# Ex_8_LED_PCB_SMD_OPM-AMP.net
KiCad netlist of a schematic drawn in EAGLE
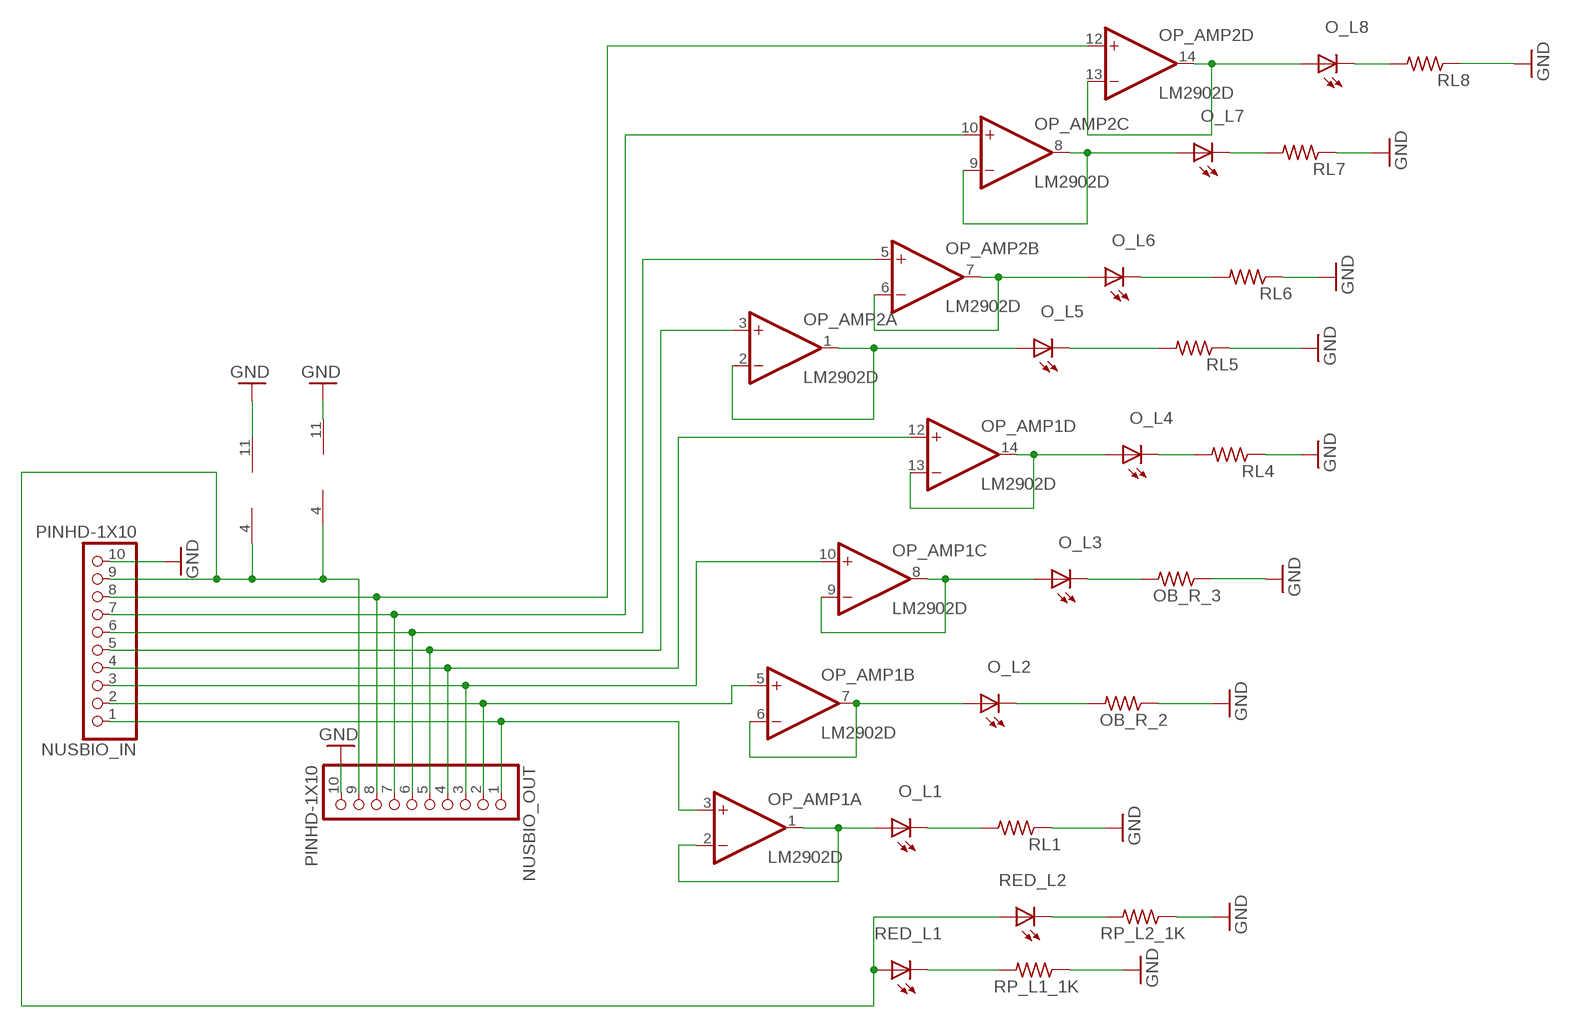
[diagram p0: schematic, sheet 1]

(export (version "E")
  (design (tool "Eeschema 10.0.6"))
  (components
    (comp (ref "NUSBIO_IN")
      (value "PINHD-1X10")
      (footprint "eagle-import:1X10-BIG")
      (libsource (lib "eagle-import") (part "PINHD-1X10"))
    )
    (comp (ref "NUSBIO_OUT")
      (value "PINHD-1X10")
      (footprint "eagle-import:1X10-BIG")
      (libsource (lib "eagle-import") (part "PINHD-1X10"))
    )
    (comp (ref "OB_R_2")
      (value "R-US_R0805")
      (footprint "eagle-import:R0805")
      (libsource (lib "eagle-import") (part "R-US_R0805"))
    )
    (comp (ref "OB_R_3")
      (value "R-US_R0805")
      (footprint "eagle-import:R0805")
      (libsource (lib "eagle-import") (part "R-US_R0805"))
    )
    (comp (ref "OP_AMP1")
      (value "LM2902D")
      (footprint "eagle-import:SO14")
      (libsource (lib "eagle-import") (part "LM2902D"))
    )
    (comp (ref "OP_AMP2")
      (value "LM2902D")
      (footprint "eagle-import:SO14")
      (libsource (lib "eagle-import") (part "LM2902D"))
    )
    (comp (ref "O_L1")
      (value "LEDCHIPLED_0805")
      (footprint "eagle-import:CHIPLED_0805")
      (libsource (lib "eagle-import") (part "LEDCHIPLED_0805"))
    )
    (comp (ref "O_L2")
      (value "LEDCHIPLED_0805")
      (footprint "eagle-import:CHIPLED_0805")
      (libsource (lib "eagle-import") (part "LEDCHIPLED_0805"))
    )
    (comp (ref "O_L3")
      (value "LEDCHIPLED_0805")
      (footprint "eagle-import:CHIPLED_0805")
      (libsource (lib "eagle-import") (part "LEDCHIPLED_0805"))
    )
    (comp (ref "O_L4")
      (value "LEDCHIPLED_0805")
      (footprint "eagle-import:CHIPLED_0805")
      (libsource (lib "eagle-import") (part "LEDCHIPLED_0805"))
    )
    (comp (ref "O_L5")
      (value "LEDCHIPLED_0805")
      (footprint "eagle-import:CHIPLED_0805")
      (libsource (lib "eagle-import") (part "LEDCHIPLED_0805"))
    )
    (comp (ref "O_L6")
      (value "LEDCHIPLED_0805")
      (footprint "eagle-import:CHIPLED_0805")
      (libsource (lib "eagle-import") (part "LEDCHIPLED_0805"))
    )
    (comp (ref "O_L7")
      (value "LEDCHIPLED_0805")
      (footprint "eagle-import:CHIPLED_0805")
      (libsource (lib "eagle-import") (part "LEDCHIPLED_0805"))
    )
    (comp (ref "O_L8")
      (value "LEDCHIPLED_0805")
      (footprint "eagle-import:CHIPLED_0805")
      (libsource (lib "eagle-import") (part "LEDCHIPLED_0805"))
    )
    (comp (ref "RED_L1")
      (value "LEDCHIPLED_0805")
      (footprint "eagle-import:CHIPLED_0805")
      (libsource (lib "eagle-import") (part "LEDCHIPLED_0805"))
    )
    (comp (ref "RED_L2")
      (value "LEDCHIPLED_0805")
      (footprint "eagle-import:CHIPLED_0805")
      (libsource (lib "eagle-import") (part "LEDCHIPLED_0805"))
    )
    (comp (ref "RL1")
      (value "R-US_R0805")
      (footprint "eagle-import:R0805")
      (libsource (lib "eagle-import") (part "R-US_R0805"))
    )
    (comp (ref "RL4")
      (value "R-US_R0805")
      (footprint "eagle-import:R0805")
      (libsource (lib "eagle-import") (part "R-US_R0805"))
    )
    (comp (ref "RL5")
      (value "R-US_R0805")
      (footprint "eagle-import:R0805")
      (libsource (lib "eagle-import") (part "R-US_R0805"))
    )
    (comp (ref "RL6")
      (value "R-US_R0805")
      (footprint "eagle-import:R0805")
      (libsource (lib "eagle-import") (part "R-US_R0805"))
    )
    (comp (ref "RL7")
      (value "R-US_R0805")
      (footprint "eagle-import:R0805")
      (libsource (lib "eagle-import") (part "R-US_R0805"))
    )
    (comp (ref "RL8")
      (value "R-US_R0805")
      (footprint "eagle-import:R0805")
      (libsource (lib "eagle-import") (part "R-US_R0805"))
    )
    (comp (ref "RP_L1_1K")
      (value "R-US_R0805")
      (footprint "eagle-import:R0805")
      (libsource (lib "eagle-import") (part "R-US_R0805"))
    )
    (comp (ref "RP_L2_1K")
      (value "R-US_R0805")
      (footprint "eagle-import:R0805")
      (libsource (lib "eagle-import") (part "R-US_R0805"))
    )
  )
  (nets
    (net (code "1") (name "GND") (class "Default")
      (node (ref "NUSBIO_IN") (pin "10") (pinfunction "10_10") (pintype "passive"))
      (node (ref "NUSBIO_OUT") (pin "10") (pinfunction "10_10") (pintype "passive"))
      (node (ref "OB_R_2") (pin "1") (pinfunction "1_1") (pintype "passive"))
      (node (ref "OB_R_3") (pin "1") (pinfunction "1_1") (pintype "passive"))
      (node (ref "OP_AMP1") (pin "11") (pinfunction "V-_11") (pintype "power_in"))
      (node (ref "OP_AMP2") (pin "11") (pinfunction "V-_11") (pintype "power_in"))
      (node (ref "RL1") (pin "1") (pinfunction "1_1") (pintype "passive"))
      (node (ref "RL4") (pin "1") (pinfunction "1_1") (pintype "passive"))
      (node (ref "RL5") (pin "1") (pinfunction "1_1") (pintype "passive"))
      (node (ref "RL6") (pin "1") (pinfunction "1_1") (pintype "passive"))
      (node (ref "RL7") (pin "1") (pinfunction "1_1") (pintype "passive"))
      (node (ref "RL8") (pin "1") (pinfunction "1_1") (pintype "passive"))
      (node (ref "RP_L1_1K") (pin "1") (pinfunction "1_1") (pintype "passive"))
      (node (ref "RP_L2_1K") (pin "1") (pinfunction "1_1") (pintype "passive"))
    )
    (net (code "2") (name "Net-(OB_R_2-Pad2)") (class "Default")
      (node (ref "OB_R_2") (pin "2") (pinfunction "2_2") (pintype "passive"))
      (node (ref "O_L2") (pin "C") (pinfunction "C_C") (pintype "passive"))
    )
    (net (code "3") (name "Net-(OB_R_3-Pad2)") (class "Default")
      (node (ref "OB_R_3") (pin "2") (pinfunction "2_2") (pintype "passive"))
      (node (ref "O_L3") (pin "C") (pinfunction "C_C") (pintype "passive"))
    )
    (net (code "4") (name "Net-(OP_AMP1A-+IN)") (class "Default")
      (node (ref "NUSBIO_IN") (pin "1") (pinfunction "1_1") (pintype "passive"))
      (node (ref "NUSBIO_OUT") (pin "1") (pinfunction "1_1") (pintype "passive"))
      (node (ref "OP_AMP1") (pin "3") (pinfunction "+IN_3") (pintype "input"))
    )
    (net (code "5") (name "Net-(OP_AMP1A--IN)") (class "Default")
      (node (ref "OP_AMP1") (pin "1") (pinfunction "OUT_1") (pintype "output"))
      (node (ref "OP_AMP1") (pin "2") (pinfunction "-IN_2") (pintype "input"))
      (node (ref "O_L1") (pin "A") (pinfunction "A_A") (pintype "passive"))
    )
    (net (code "6") (name "Net-(OP_AMP1B-+IN)") (class "Default")
      (node (ref "NUSBIO_IN") (pin "2") (pinfunction "2_2") (pintype "passive"))
      (node (ref "NUSBIO_OUT") (pin "2") (pinfunction "2_2") (pintype "passive"))
      (node (ref "OP_AMP1") (pin "5") (pinfunction "+IN_5") (pintype "input"))
    )
    (net (code "7") (name "Net-(OP_AMP1B--IN)") (class "Default")
      (node (ref "OP_AMP1") (pin "6") (pinfunction "-IN_6") (pintype "input"))
      (node (ref "OP_AMP1") (pin "7") (pinfunction "OUT_7") (pintype "output"))
      (node (ref "O_L2") (pin "A") (pinfunction "A_A") (pintype "passive"))
    )
    (net (code "8") (name "Net-(OP_AMP1C-+IN)") (class "Default")
      (node (ref "NUSBIO_IN") (pin "3") (pinfunction "3_3") (pintype "passive"))
      (node (ref "NUSBIO_OUT") (pin "3") (pinfunction "3_3") (pintype "passive"))
      (node (ref "OP_AMP1") (pin "10") (pinfunction "+IN_10") (pintype "input"))
    )
    (net (code "9") (name "Net-(OP_AMP1C--IN)") (class "Default")
      (node (ref "OP_AMP1") (pin "8") (pinfunction "OUT_8") (pintype "output"))
      (node (ref "OP_AMP1") (pin "9") (pinfunction "-IN_9") (pintype "input"))
      (node (ref "O_L3") (pin "A") (pinfunction "A_A") (pintype "passive"))
    )
    (net (code "10") (name "Net-(OP_AMP1D-+IN)") (class "Default")
      (node (ref "NUSBIO_IN") (pin "4") (pinfunction "4_4") (pintype "passive"))
      (node (ref "NUSBIO_OUT") (pin "4") (pinfunction "4_4") (pintype "passive"))
      (node (ref "OP_AMP1") (pin "12") (pinfunction "+IN_12") (pintype "input"))
    )
    (net (code "11") (name "Net-(OP_AMP1D--IN)") (class "Default")
      (node (ref "OP_AMP1") (pin "13") (pinfunction "-IN_13") (pintype "input"))
      (node (ref "OP_AMP1") (pin "14") (pinfunction "OUT_14") (pintype "output"))
      (node (ref "O_L4") (pin "A") (pinfunction "A_A") (pintype "passive"))
    )
    (net (code "12") (name "Net-(OP_AMP1E-V+)") (class "Default")
      (node (ref "NUSBIO_IN") (pin "9") (pinfunction "9_9") (pintype "passive"))
      (node (ref "NUSBIO_OUT") (pin "9") (pinfunction "9_9") (pintype "passive"))
      (node (ref "OP_AMP1") (pin "4") (pinfunction "V+_4") (pintype "power_in"))
      (node (ref "OP_AMP2") (pin "4") (pinfunction "V+_4") (pintype "power_in"))
      (node (ref "RED_L1") (pin "A") (pinfunction "A_A") (pintype "passive"))
      (node (ref "RED_L2") (pin "A") (pinfunction "A_A") (pintype "passive"))
    )
    (net (code "13") (name "Net-(OP_AMP2A-+IN)") (class "Default")
      (node (ref "NUSBIO_IN") (pin "5") (pinfunction "5_5") (pintype "passive"))
      (node (ref "NUSBIO_OUT") (pin "5") (pinfunction "5_5") (pintype "passive"))
      (node (ref "OP_AMP2") (pin "3") (pinfunction "+IN_3") (pintype "input"))
    )
    (net (code "14") (name "Net-(OP_AMP2A--IN)") (class "Default")
      (node (ref "OP_AMP2") (pin "1") (pinfunction "OUT_1") (pintype "output"))
      (node (ref "OP_AMP2") (pin "2") (pinfunction "-IN_2") (pintype "input"))
      (node (ref "O_L5") (pin "A") (pinfunction "A_A") (pintype "passive"))
    )
    (net (code "15") (name "Net-(OP_AMP2B-+IN)") (class "Default")
      (node (ref "NUSBIO_IN") (pin "6") (pinfunction "6_6") (pintype "passive"))
      (node (ref "NUSBIO_OUT") (pin "6") (pinfunction "6_6") (pintype "passive"))
      (node (ref "OP_AMP2") (pin "5") (pinfunction "+IN_5") (pintype "input"))
    )
    (net (code "16") (name "Net-(OP_AMP2B--IN)") (class "Default")
      (node (ref "OP_AMP2") (pin "6") (pinfunction "-IN_6") (pintype "input"))
      (node (ref "OP_AMP2") (pin "7") (pinfunction "OUT_7") (pintype "output"))
      (node (ref "O_L6") (pin "A") (pinfunction "A_A") (pintype "passive"))
    )
    (net (code "17") (name "Net-(OP_AMP2C-+IN)") (class "Default")
      (node (ref "NUSBIO_IN") (pin "7") (pinfunction "7_7") (pintype "passive"))
      (node (ref "NUSBIO_OUT") (pin "7") (pinfunction "7_7") (pintype "passive"))
      (node (ref "OP_AMP2") (pin "10") (pinfunction "+IN_10") (pintype "input"))
    )
    (net (code "18") (name "Net-(OP_AMP2C--IN)") (class "Default")
      (node (ref "OP_AMP2") (pin "8") (pinfunction "OUT_8") (pintype "output"))
      (node (ref "OP_AMP2") (pin "9") (pinfunction "-IN_9") (pintype "input"))
      (node (ref "O_L7") (pin "A") (pinfunction "A_A") (pintype "passive"))
    )
    (net (code "19") (name "Net-(OP_AMP2D-+IN)") (class "Default")
      (node (ref "NUSBIO_IN") (pin "8") (pinfunction "8_8") (pintype "passive"))
      (node (ref "NUSBIO_OUT") (pin "8") (pinfunction "8_8") (pintype "passive"))
      (node (ref "OP_AMP2") (pin "12") (pinfunction "+IN_12") (pintype "input"))
    )
    (net (code "20") (name "Net-(OP_AMP2D--IN)") (class "Default")
      (node (ref "OP_AMP2") (pin "13") (pinfunction "-IN_13") (pintype "input"))
      (node (ref "OP_AMP2") (pin "14") (pinfunction "OUT_14") (pintype "output"))
      (node (ref "O_L8") (pin "A") (pinfunction "A_A") (pintype "passive"))
    )
    (net (code "21") (name "Net-(O_L1-PadC)") (class "Default")
      (node (ref "O_L1") (pin "C") (pinfunction "C_C") (pintype "passive"))
      (node (ref "RL1") (pin "2") (pinfunction "2_2") (pintype "passive"))
    )
    (net (code "22") (name "Net-(O_L4-PadC)") (class "Default")
      (node (ref "O_L4") (pin "C") (pinfunction "C_C") (pintype "passive"))
      (node (ref "RL4") (pin "2") (pinfunction "2_2") (pintype "passive"))
    )
    (net (code "23") (name "Net-(O_L5-PadC)") (class "Default")
      (node (ref "O_L5") (pin "C") (pinfunction "C_C") (pintype "passive"))
      (node (ref "RL5") (pin "2") (pinfunction "2_2") (pintype "passive"))
    )
    (net (code "24") (name "Net-(O_L6-PadC)") (class "Default")
      (node (ref "O_L6") (pin "C") (pinfunction "C_C") (pintype "passive"))
      (node (ref "RL6") (pin "2") (pinfunction "2_2") (pintype "passive"))
    )
    (net (code "25") (name "Net-(O_L7-PadC)") (class "Default")
      (node (ref "O_L7") (pin "C") (pinfunction "C_C") (pintype "passive"))
      (node (ref "RL7") (pin "2") (pinfunction "2_2") (pintype "passive"))
    )
    (net (code "26") (name "Net-(O_L8-PadC)") (class "Default")
      (node (ref "O_L8") (pin "C") (pinfunction "C_C") (pintype "passive"))
      (node (ref "RL8") (pin "2") (pinfunction "2_2") (pintype "passive"))
    )
    (net (code "27") (name "Net-(RED_L1-PadC)") (class "Default")
      (node (ref "RED_L1") (pin "C") (pinfunction "C_C") (pintype "passive"))
      (node (ref "RP_L1_1K") (pin "2") (pinfunction "2_2") (pintype "passive"))
    )
    (net (code "28") (name "Net-(RED_L2-PadC)") (class "Default")
      (node (ref "RED_L2") (pin "C") (pinfunction "C_C") (pintype "passive"))
      (node (ref "RP_L2_1K") (pin "2") (pinfunction "2_2") (pintype "passive"))
    )
  )
)
